# dronesel3.net
KiCad netlist of a schematic drawn in EAGLE
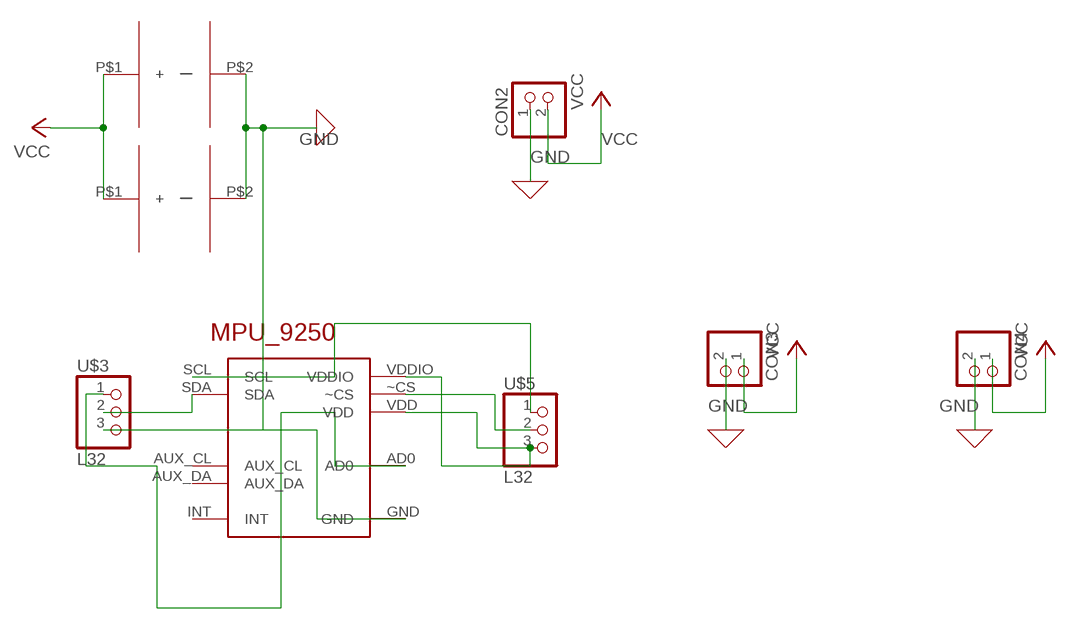
[diagram p0: schematic, sheet 1]

(export (version "E")
  (design (tool "Eeschema 10.0.6"))
  (components
    (comp (ref "CON2")
      (value "L2")
      (footprint "eagle-import:L_2")
      (libsource (lib "eagle-import") (part "L2"))
    )
    (comp (ref "CON3")
      (value "L2")
      (footprint "eagle-import:L_2")
      (libsource (lib "eagle-import") (part "L2"))
    )
    (comp (ref "CON4")
      (value "L2")
      (footprint "eagle-import:L_2")
      (libsource (lib "eagle-import") (part "L2"))
    )
    (comp (ref "MPU9250")
      (value "MPU_9250")
      (footprint "eagle-import:MPU_9250")
      (libsource (lib "eagle-import") (part "MPU_9250"))
    )
    (comp (ref "U$1")
      (value "VEC5R4355QG-I")
      (footprint "eagle-import:VEC5R4355QG-I")
      (libsource (lib "eagle-import") (part "VEC5R4355QG-I"))
    )
    (comp (ref "U$2")
      (value "VEC5R4355QG-I")
      (footprint "eagle-import:VEC5R4355QG-I")
      (libsource (lib "eagle-import") (part "VEC5R4355QG-I"))
    )
    (comp (ref "U$3")
      (value "L32")
      (footprint "eagle-import:L_32")
      (libsource (lib "eagle-import") (part "L32"))
    )
    (comp (ref "U$5")
      (value "L32")
      (footprint "eagle-import:L_32")
      (libsource (lib "eagle-import") (part "L32"))
    )
  )
  (nets
    (net (code "1") (name "GND") (class "Default")
      (node (ref "CON2") (pin "1") (pinfunction "1_1") (pintype "passive"))
      (node (ref "CON3") (pin "2") (pinfunction "2_2") (pintype "passive"))
      (node (ref "CON4") (pin "2") (pinfunction "2_2") (pintype "passive"))
      (node (ref "MPU9250") (pin "GND") (pinfunction "GND_GND") (pintype "bidirectional"))
      (node (ref "U$1") (pin "P$2") (pinfunction "ー_P$2") (pintype "bidirectional"))
      (node (ref "U$2") (pin "P$2") (pinfunction "ー_P$2") (pintype "bidirectional"))
      (node (ref "U$3") (pin "3") (pinfunction "3_3") (pintype "passive"))
    )
    (net (code "2") (name "Net-(MPU9250-PadAD0)") (class "Default")
      (node (ref "MPU9250") (pin "AD0") (pinfunction "AD0_AD0") (pintype "bidirectional"))
      (node (ref "U$3") (pin "1") (pinfunction "1_1") (pintype "passive"))
    )
    (net (code "3") (name "Net-(MPU9250-PadSCL)") (class "Default")
      (node (ref "MPU9250") (pin "SCL") (pinfunction "SCL_SCL") (pintype "bidirectional"))
      (node (ref "U$5") (pin "1") (pinfunction "1_1") (pintype "passive"))
    )
    (net (code "4") (name "Net-(MPU9250-PadSDA)") (class "Default")
      (node (ref "MPU9250") (pin "SDA") (pinfunction "SDA_SDA") (pintype "bidirectional"))
      (node (ref "U$3") (pin "2") (pinfunction "2_2") (pintype "passive"))
    )
    (net (code "5") (name "Net-(MPU9250-PadVDD)") (class "Default")
      (node (ref "MPU9250") (pin "VDD") (pinfunction "VDD_VDD") (pintype "bidirectional"))
      (node (ref "MPU9250") (pin "VDDIO") (pinfunction "VDDIO_VDDIO") (pintype "bidirectional"))
      (node (ref "U$5") (pin "3") (pinfunction "3_3") (pintype "passive"))
    )
    (net (code "6") (name "Net-(MPU9250-~{CS})") (class "Default")
      (node (ref "MPU9250") (pin "~CS") (pinfunction "~{CS}_~CS") (pintype "bidirectional"))
      (node (ref "U$5") (pin "2") (pinfunction "2_2") (pintype "passive"))
    )
    (net (code "7") (name "VCC") (class "Default")
      (node (ref "CON2") (pin "2") (pinfunction "2_2") (pintype "passive"))
      (node (ref "CON3") (pin "1") (pinfunction "1_1") (pintype "passive"))
      (node (ref "CON4") (pin "1") (pinfunction "1_1") (pintype "passive"))
      (node (ref "U$1") (pin "P$1") (pinfunction "+_P$1") (pintype "bidirectional"))
      (node (ref "U$2") (pin "P$1") (pinfunction "+_P$1") (pintype "bidirectional"))
    )
    (net (code "8") (name "unconnected-(MPU9250-PadAUX_CL)") (class "Default")
      (node (ref "MPU9250") (pin "AUX_CL") (pinfunction "AUX_CL_AUX_CL") (pintype "bidirectional"))
    )
    (net (code "9") (name "unconnected-(MPU9250-PadAUX_DA)") (class "Default")
      (node (ref "MPU9250") (pin "AUX_DA") (pinfunction "AUX_DA_AUX_DA") (pintype "bidirectional"))
    )
    (net (code "10") (name "unconnected-(MPU9250-PadINT)") (class "Default")
      (node (ref "MPU9250") (pin "INT") (pinfunction "INT_INT") (pintype "bidirectional"))
    )
  )
)
